# rpi-can-rs485.net
KiCad netlist of a schematic drawn in EAGLE
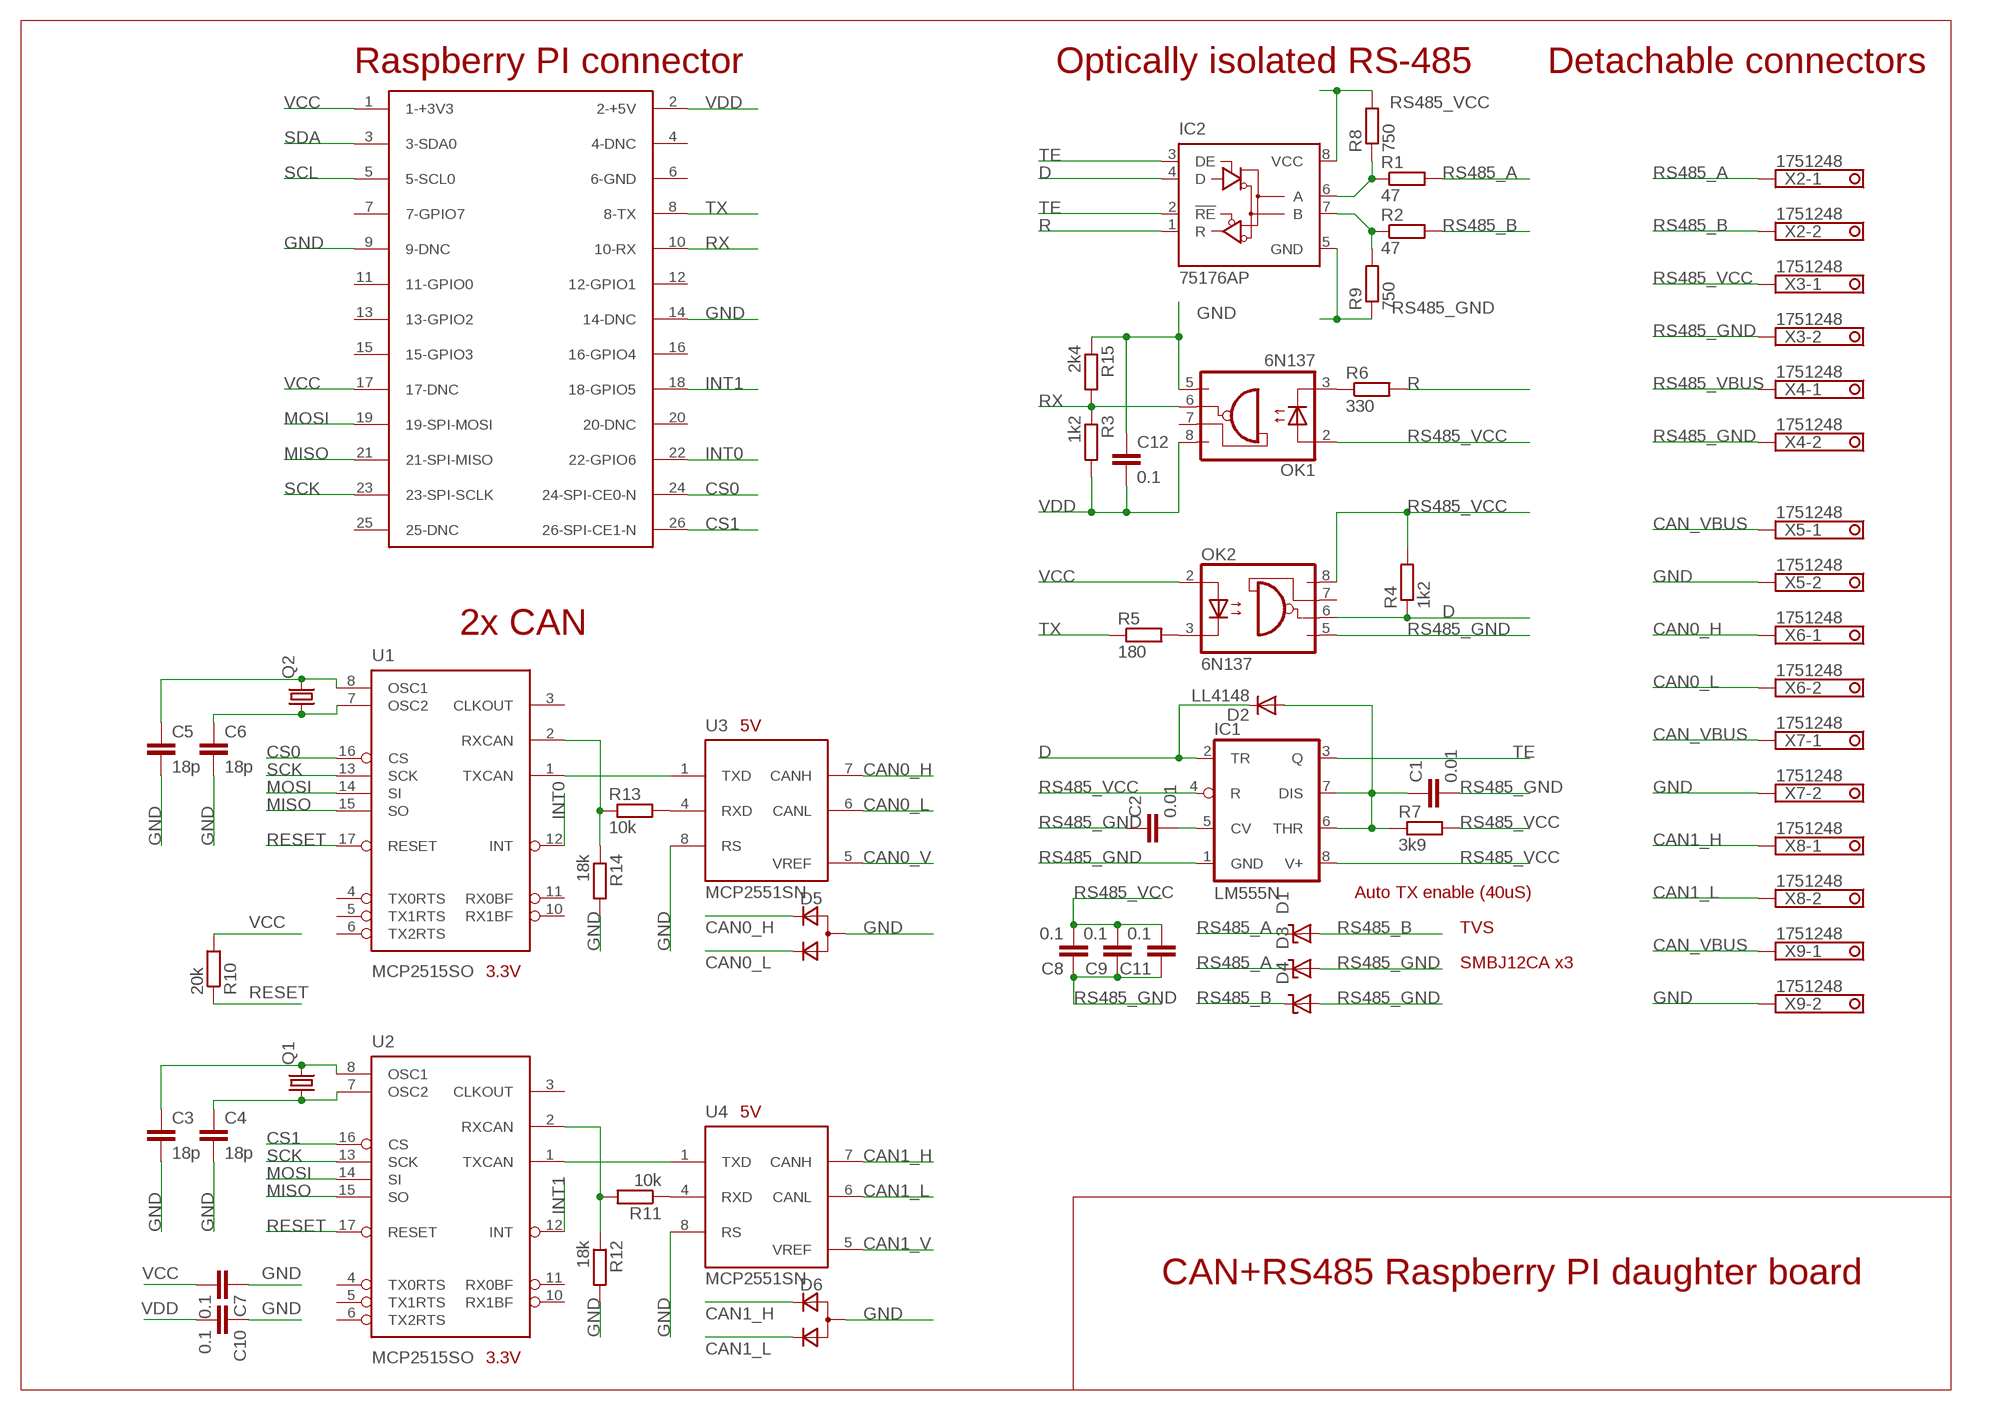
[diagram p0: schematic, sheet 1]

(export (version "E")
  (design (tool "Eeschema 10.0.6"))
  (components
    (comp (ref "C1")
      (value "0.01")
      (footprint "eagle-import:C0805")
      (libsource (lib "eagle-import") (part "C-EUC0805"))
    )
    (comp (ref "C2")
      (value "0.01")
      (footprint "eagle-import:C0805")
      (libsource (lib "eagle-import") (part "C-EUC0805"))
    )
    (comp (ref "C3")
      (value "18p")
      (footprint "eagle-import:C0805")
      (libsource (lib "eagle-import") (part "C-EUC0805"))
    )
    (comp (ref "C4")
      (value "18p")
      (footprint "eagle-import:C0805")
      (libsource (lib "eagle-import") (part "C-EUC0805"))
    )
    (comp (ref "C5")
      (value "18p")
      (footprint "eagle-import:C0805")
      (libsource (lib "eagle-import") (part "C-EUC0805"))
    )
    (comp (ref "C6")
      (value "18p")
      (footprint "eagle-import:C0805")
      (libsource (lib "eagle-import") (part "C-EUC0805"))
    )
    (comp (ref "C7")
      (value "0.1")
      (footprint "eagle-import:C1206")
      (libsource (lib "eagle-import") (part "C-EUC1206"))
    )
    (comp (ref "C8")
      (value "0.1")
      (footprint "eagle-import:C0805")
      (libsource (lib "eagle-import") (part "C-EUC0805"))
    )
    (comp (ref "C9")
      (value "0.1")
      (footprint "eagle-import:C0805")
      (libsource (lib "eagle-import") (part "C-EUC0805"))
    )
    (comp (ref "C10")
      (value "0.1")
      (footprint "eagle-import:C0805")
      (libsource (lib "eagle-import") (part "C-EUC0805"))
    )
    (comp (ref "C11")
      (value "0.1")
      (footprint "eagle-import:C1206")
      (libsource (lib "eagle-import") (part "C-EUC1206"))
    )
    (comp (ref "C12")
      (value "0.1")
      (footprint "eagle-import:C1206")
      (libsource (lib "eagle-import") (part "C-EUC1206"))
    )
    (comp (ref "D1")
      (value "SUPPRESSOR-SMBJ")
      (footprint "eagle-import:SMBJ")
      (libsource (lib "eagle-import") (part "SUPPRESSOR-SMBJ"))
    )
    (comp (ref "D2")
      (value "LL4148")
      (footprint "eagle-import:SOD80C")
      (libsource (lib "eagle-import") (part "DIODE-SOD80C"))
    )
    (comp (ref "D3")
      (value "SUPPRESSOR-SMBJ")
      (footprint "eagle-import:SMBJ")
      (libsource (lib "eagle-import") (part "SUPPRESSOR-SMBJ"))
    )
    (comp (ref "D4")
      (value "SUPPRESSOR-SMBJ")
      (footprint "eagle-import:SMBJ")
      (libsource (lib "eagle-import") (part "SUPPRESSOR-SMBJ"))
    )
    (comp (ref "D5")
      (value "D_2CSOT323")
      (footprint "eagle-import:SOT323")
      (libsource (lib "eagle-import") (part "D_2CSOT323"))
    )
    (comp (ref "D6")
      (value "D_2CSOT323")
      (footprint "eagle-import:SOT323")
      (libsource (lib "eagle-import") (part "D_2CSOT323"))
    )
    (comp (ref "IC1")
      (value "LM555N")
      (footprint "eagle-import:DIL08")
      (libsource (lib "eagle-import") (part "555NLM"))
    )
    (comp (ref "IC2")
      (value "75176AP")
      (footprint "eagle-import:DIL08")
      (libsource (lib "eagle-import") (part "75176AP"))
    )
    (comp (ref "OK1")
      (value "6N137")
      (footprint "eagle-import:DIL08")
      (libsource (lib "eagle-import") (part "6N137"))
    )
    (comp (ref "OK2")
      (value "6N137")
      (footprint "eagle-import:DIL08")
      (libsource (lib "eagle-import") (part "6N137"))
    )
    (comp (ref "Q1")
      (value "CRYSTALHC49S")
      (footprint "eagle-import:HC49_S")
      (libsource (lib "eagle-import") (part "CRYSTALHC49S"))
    )
    (comp (ref "Q2")
      (value "CRYSTALHC49S")
      (footprint "eagle-import:HC49_S")
      (libsource (lib "eagle-import") (part "CRYSTALHC49S"))
    )
    (comp (ref "R1")
      (value "47")
      (footprint "eagle-import:R1206")
      (libsource (lib "eagle-import") (part "R-EU_R1206"))
    )
    (comp (ref "R2")
      (value "47")
      (footprint "eagle-import:R1206")
      (libsource (lib "eagle-import") (part "R-EU_R1206"))
    )
    (comp (ref "R3")
      (value "1k2")
      (footprint "eagle-import:R0805")
      (libsource (lib "eagle-import") (part "R-EU_R0805"))
    )
    (comp (ref "R4")
      (value "1k2")
      (footprint "eagle-import:R0805")
      (libsource (lib "eagle-import") (part "R-EU_R0805"))
    )
    (comp (ref "R5")
      (value "180")
      (footprint "eagle-import:R0805")
      (libsource (lib "eagle-import") (part "R-EU_R0805"))
    )
    (comp (ref "R6")
      (value "330")
      (footprint "eagle-import:R0805")
      (libsource (lib "eagle-import") (part "R-EU_R0805"))
    )
    (comp (ref "R7")
      (value "3k9")
      (footprint "eagle-import:R0805")
      (libsource (lib "eagle-import") (part "R-EU_R0805"))
    )
    (comp (ref "R8")
      (value "750")
      (footprint "eagle-import:R1206")
      (libsource (lib "eagle-import") (part "R-EU_R1206"))
    )
    (comp (ref "R9")
      (value "750")
      (footprint "eagle-import:R1206")
      (libsource (lib "eagle-import") (part "R-EU_R1206"))
    )
    (comp (ref "R10")
      (value "20k")
      (footprint "eagle-import:R0805")
      (libsource (lib "eagle-import") (part "R-EU_R0805"))
    )
    (comp (ref "R11")
      (value "10k")
      (footprint "eagle-import:R0805")
      (libsource (lib "eagle-import") (part "R-EU_R0805"))
    )
    (comp (ref "R12")
      (value "18k")
      (footprint "eagle-import:R0805")
      (libsource (lib "eagle-import") (part "R-EU_R0805"))
    )
    (comp (ref "R13")
      (value "10k")
      (footprint "eagle-import:R0805")
      (libsource (lib "eagle-import") (part "R-EU_R0805"))
    )
    (comp (ref "R14")
      (value "18k")
      (footprint "eagle-import:R0805")
      (libsource (lib "eagle-import") (part "R-EU_R0805"))
    )
    (comp (ref "R15")
      (value "2k4")
      (footprint "eagle-import:R0805")
      (libsource (lib "eagle-import") (part "R-EU_R0805"))
    )
    (comp (ref "U$1")
      (value "RASPBERRY-PI")
      (footprint "eagle-import:RASPBERRY-PI")
      (libsource (lib "eagle-import") (part "RASPBERRY-PI"))
    )
    (comp (ref "U1")
      (value "MCP2515SO")
      (footprint "eagle-import:SO-18W")
      (libsource (lib "eagle-import") (part "MCP2510SO"))
    )
    (comp (ref "U2")
      (value "MCP2515SO")
      (footprint "eagle-import:SO-18W")
      (libsource (lib "eagle-import") (part "MCP2510SO"))
    )
    (comp (ref "U3")
      (value "MCP2551SN")
      (footprint "eagle-import:SO-08")
      (libsource (lib "eagle-import") (part "MCP2551SN"))
    )
    (comp (ref "U4")
      (value "MCP2551SN")
      (footprint "eagle-import:SO-08")
      (libsource (lib "eagle-import") (part "MCP2551SN"))
    )
    (comp (ref "X2")
      (value "1751248")
      (footprint "eagle-import:1751248")
      (libsource (lib "eagle-import") (part "1751248"))
    )
    (comp (ref "X3")
      (value "1751248")
      (footprint "eagle-import:1751248")
      (libsource (lib "eagle-import") (part "1751248"))
    )
    (comp (ref "X4")
      (value "1751248")
      (footprint "eagle-import:1751248")
      (libsource (lib "eagle-import") (part "1751248"))
    )
    (comp (ref "X5")
      (value "1751248")
      (footprint "eagle-import:1751248")
      (libsource (lib "eagle-import") (part "1751248"))
    )
    (comp (ref "X6")
      (value "1751248")
      (footprint "eagle-import:1751248")
      (libsource (lib "eagle-import") (part "1751248"))
    )
    (comp (ref "X7")
      (value "1751248")
      (footprint "eagle-import:1751248")
      (libsource (lib "eagle-import") (part "1751248"))
    )
    (comp (ref "X8")
      (value "1751248")
      (footprint "eagle-import:1751248")
      (libsource (lib "eagle-import") (part "1751248"))
    )
    (comp (ref "X9")
      (value "1751248")
      (footprint "eagle-import:1751248")
      (fields (field (name "OC_FARNELL") "unknown") (field (name "OC_NEWARK") "unknown"))
      (libsource (lib "eagle-import") (part "1751248"))
    )
  )
  (nets
    (net (code "1") (name "/CAN0_H") (class "Default")
      (node (ref "D5") (pin "2") (pinfunction "C1_2") (pintype "passive"))
      (node (ref "U3") (pin "7") (pinfunction "CANH_7") (pintype "bidirectional"))
      (node (ref "X6") (pin "1") (pinfunction "K_1") (pintype "passive"))
    )
    (net (code "2") (name "/CAN0_L") (class "Default")
      (node (ref "D5") (pin "3") (pinfunction "C2_3") (pintype "passive"))
      (node (ref "U3") (pin "6") (pinfunction "CANL_6") (pintype "bidirectional"))
      (node (ref "X6") (pin "2") (pinfunction "K_2") (pintype "passive"))
    )
    (net (code "3") (name "/CAN0_V") (class "Default")
      (node (ref "U3") (pin "5") (pinfunction "VREF_5") (pintype "power_in"))
    )
    (net (code "4") (name "/CAN1_H") (class "Default")
      (node (ref "D6") (pin "2") (pinfunction "C1_2") (pintype "passive"))
      (node (ref "U4") (pin "7") (pinfunction "CANH_7") (pintype "bidirectional"))
      (node (ref "X8") (pin "1") (pinfunction "K_1") (pintype "passive"))
    )
    (net (code "5") (name "/CAN1_L") (class "Default")
      (node (ref "D6") (pin "3") (pinfunction "C2_3") (pintype "passive"))
      (node (ref "U4") (pin "6") (pinfunction "CANL_6") (pintype "bidirectional"))
      (node (ref "X8") (pin "2") (pinfunction "K_2") (pintype "passive"))
    )
    (net (code "6") (name "/CAN1_V") (class "Default")
      (node (ref "U4") (pin "5") (pinfunction "VREF_5") (pintype "power_in"))
    )
    (net (code "7") (name "/CAN_VBUS") (class "Default")
      (node (ref "X5") (pin "1") (pinfunction "K_1") (pintype "passive"))
      (node (ref "X7") (pin "1") (pinfunction "K_1") (pintype "passive"))
      (node (ref "X9") (pin "1") (pinfunction "K_1") (pintype "passive"))
    )
    (net (code "8") (name "/CS0") (class "Default")
      (node (ref "U$1") (pin "24") (pinfunction "24-SPI-CE0-N_24") (pintype "bidirectional"))
      (node (ref "U1") (pin "16") (pinfunction "CS_16") (pintype "input"))
    )
    (net (code "9") (name "/CS1") (class "Default")
      (node (ref "U$1") (pin "26") (pinfunction "26-SPI-CE1-N_26") (pintype "bidirectional"))
      (node (ref "U2") (pin "16") (pinfunction "CS_16") (pintype "input"))
    )
    (net (code "10") (name "/D") (class "Default")
      (node (ref "D2") (pin "C") (pinfunction "C_C") (pintype "passive"))
      (node (ref "IC1") (pin "2") (pinfunction "TR_2") (pintype "input"))
      (node (ref "IC2") (pin "4") (pinfunction "D_4") (pintype "input"))
      (node (ref "OK2") (pin "6") (pinfunction "VO_6") (pintype "passive"))
      (node (ref "R4") (pin "1") (pinfunction "1_1") (pintype "passive"))
    )
    (net (code "11") (name "/GND") (class "Default")
      (node (ref "C10") (pin "1") (pinfunction "1_1") (pintype "passive"))
      (node (ref "C12") (pin "1") (pinfunction "1_1") (pintype "passive"))
      (node (ref "C3") (pin "2") (pinfunction "2_2") (pintype "passive"))
      (node (ref "C4") (pin "2") (pinfunction "2_2") (pintype "passive"))
      (node (ref "C5") (pin "2") (pinfunction "2_2") (pintype "passive"))
      (node (ref "C6") (pin "2") (pinfunction "2_2") (pintype "passive"))
      (node (ref "C7") (pin "1") (pinfunction "1_1") (pintype "passive"))
      (node (ref "D5") (pin "1") (pinfunction "A_1") (pintype "passive"))
      (node (ref "D6") (pin "1") (pinfunction "A_1") (pintype "passive"))
      (node (ref "OK1") (pin "5") (pinfunction "GND_5") (pintype "passive"))
      (node (ref "R12") (pin "2") (pinfunction "2_2") (pintype "passive"))
      (node (ref "R14") (pin "2") (pinfunction "2_2") (pintype "passive"))
      (node (ref "R15") (pin "1") (pinfunction "1_1") (pintype "passive"))
      (node (ref "U$1") (pin "14") (pinfunction "14-DNC_14") (pintype "bidirectional"))
      (node (ref "U$1") (pin "9") (pinfunction "9-DNC_9") (pintype "bidirectional"))
      (node (ref "U3") (pin "8") (pinfunction "RS_8") (pintype "input"))
      (node (ref "U4") (pin "8") (pinfunction "RS_8") (pintype "input"))
      (node (ref "X5") (pin "2") (pinfunction "K_2") (pintype "passive"))
      (node (ref "X7") (pin "2") (pinfunction "K_2") (pintype "passive"))
      (node (ref "X9") (pin "2") (pinfunction "K_2") (pintype "passive"))
    )
    (net (code "12") (name "/INT0") (class "Default")
      (node (ref "U$1") (pin "22") (pinfunction "22-GPIO6_22") (pintype "bidirectional"))
      (node (ref "U1") (pin "12") (pinfunction "INT_12") (pintype "output"))
    )
    (net (code "13") (name "/INT1") (class "Default")
      (node (ref "U$1") (pin "18") (pinfunction "18-GPIO5_18") (pintype "bidirectional"))
      (node (ref "U2") (pin "12") (pinfunction "INT_12") (pintype "output"))
    )
    (net (code "14") (name "/MISO") (class "Default")
      (node (ref "U$1") (pin "21") (pinfunction "21-SPI-MISO_21") (pintype "bidirectional"))
      (node (ref "U1") (pin "15") (pinfunction "SO_15") (pintype "output"))
      (node (ref "U2") (pin "15") (pinfunction "SO_15") (pintype "output"))
    )
    (net (code "15") (name "/MOSI") (class "Default")
      (node (ref "U$1") (pin "19") (pinfunction "19-SPI-MOSI_19") (pintype "bidirectional"))
      (node (ref "U1") (pin "14") (pinfunction "SI_14") (pintype "input"))
      (node (ref "U2") (pin "14") (pinfunction "SI_14") (pintype "input"))
    )
    (net (code "16") (name "/R") (class "Default")
      (node (ref "IC2") (pin "1") (pinfunction "R_1") (pintype "input"))
      (node (ref "R6") (pin "2") (pinfunction "2_2") (pintype "passive"))
    )
    (net (code "17") (name "/RESET") (class "Default")
      (node (ref "R10") (pin "1") (pinfunction "1_1") (pintype "passive"))
      (node (ref "U1") (pin "17") (pinfunction "RESET_17") (pintype "input"))
      (node (ref "U2") (pin "17") (pinfunction "RESET_17") (pintype "input"))
    )
    (net (code "18") (name "/RS485_A") (class "Default")
      (node (ref "D1") (pin "C") (pinfunction "C_C") (pintype "passive"))
      (node (ref "D3") (pin "C") (pinfunction "C_C") (pintype "passive"))
      (node (ref "R1") (pin "2") (pinfunction "2_2") (pintype "passive"))
      (node (ref "X2") (pin "1") (pinfunction "K_1") (pintype "passive"))
    )
    (net (code "19") (name "/RS485_B") (class "Default")
      (node (ref "D1") (pin "A") (pinfunction "A_A") (pintype "passive"))
      (node (ref "D4") (pin "C") (pinfunction "C_C") (pintype "passive"))
      (node (ref "R2") (pin "2") (pinfunction "2_2") (pintype "passive"))
      (node (ref "X2") (pin "2") (pinfunction "K_2") (pintype "passive"))
    )
    (net (code "20") (name "/RS485_GND") (class "Default")
      (node (ref "C1") (pin "2") (pinfunction "2_2") (pintype "passive"))
      (node (ref "C11") (pin "1") (pinfunction "1_1") (pintype "passive"))
      (node (ref "C2") (pin "1") (pinfunction "1_1") (pintype "passive"))
      (node (ref "C8") (pin "1") (pinfunction "1_1") (pintype "passive"))
      (node (ref "C9") (pin "1") (pinfunction "1_1") (pintype "passive"))
      (node (ref "D3") (pin "A") (pinfunction "A_A") (pintype "passive"))
      (node (ref "D4") (pin "A") (pinfunction "A_A") (pintype "passive"))
      (node (ref "IC1") (pin "1") (pinfunction "GND_1") (pintype "power_in"))
      (node (ref "IC2") (pin "5") (pinfunction "GND_5") (pintype "power_in"))
      (node (ref "OK2") (pin "5") (pinfunction "GND_5") (pintype "passive"))
      (node (ref "R9") (pin "1") (pinfunction "1_1") (pintype "passive"))
      (node (ref "X3") (pin "2") (pinfunction "K_2") (pintype "passive"))
      (node (ref "X4") (pin "2") (pinfunction "K_2") (pintype "passive"))
    )
    (net (code "21") (name "/RS485_VBUS") (class "Default")
      (node (ref "X4") (pin "1") (pinfunction "K_1") (pintype "passive"))
    )
    (net (code "22") (name "/RS485_VCC") (class "Default")
      (node (ref "C11") (pin "2") (pinfunction "2_2") (pintype "passive"))
      (node (ref "C8") (pin "2") (pinfunction "2_2") (pintype "passive"))
      (node (ref "C9") (pin "2") (pinfunction "2_2") (pintype "passive"))
      (node (ref "IC1") (pin "4") (pinfunction "R_4") (pintype "input"))
      (node (ref "IC1") (pin "8") (pinfunction "V+_8") (pintype "power_in"))
      (node (ref "IC2") (pin "8") (pinfunction "VCC_8") (pintype "power_in"))
      (node (ref "OK1") (pin "2") (pinfunction "A_2") (pintype "passive"))
      (node (ref "OK2") (pin "8") (pinfunction "VCC_8") (pintype "passive"))
      (node (ref "R4") (pin "2") (pinfunction "2_2") (pintype "passive"))
      (node (ref "R7") (pin "2") (pinfunction "2_2") (pintype "passive"))
      (node (ref "R8") (pin "2") (pinfunction "2_2") (pintype "passive"))
      (node (ref "X3") (pin "1") (pinfunction "K_1") (pintype "passive"))
    )
    (net (code "23") (name "/RX") (class "Default")
      (node (ref "OK1") (pin "6") (pinfunction "VO_6") (pintype "passive"))
      (node (ref "R15") (pin "2") (pinfunction "2_2") (pintype "passive"))
      (node (ref "R3") (pin "1") (pinfunction "1_1") (pintype "passive"))
      (node (ref "U$1") (pin "10") (pinfunction "10-RX_10") (pintype "bidirectional"))
    )
    (net (code "24") (name "/SCK") (class "Default")
      (node (ref "U$1") (pin "23") (pinfunction "23-SPI-SCLK_23") (pintype "bidirectional"))
      (node (ref "U1") (pin "13") (pinfunction "SCK_13") (pintype "input"))
      (node (ref "U2") (pin "13") (pinfunction "SCK_13") (pintype "input"))
    )
    (net (code "25") (name "/SCL") (class "Default")
      (node (ref "U$1") (pin "5") (pinfunction "5-SCL0_5") (pintype "bidirectional"))
    )
    (net (code "26") (name "/SDA") (class "Default")
      (node (ref "U$1") (pin "3") (pinfunction "3-SDA0_3") (pintype "bidirectional"))
    )
    (net (code "27") (name "/TE") (class "Default")
      (node (ref "IC1") (pin "3") (pinfunction "Q_3") (pintype "output"))
      (node (ref "IC2") (pin "2") (pinfunction "~{RE}_2") (pintype "input"))
      (node (ref "IC2") (pin "3") (pinfunction "DE_3") (pintype "input"))
    )
    (net (code "28") (name "/TX") (class "Default")
      (node (ref "R5") (pin "1") (pinfunction "1_1") (pintype "passive"))
      (node (ref "U$1") (pin "8") (pinfunction "8-TX_8") (pintype "bidirectional"))
    )
    (net (code "29") (name "/VCC") (class "Default")
      (node (ref "C7") (pin "2") (pinfunction "2_2") (pintype "passive"))
      (node (ref "OK2") (pin "2") (pinfunction "A_2") (pintype "passive"))
      (node (ref "R10") (pin "2") (pinfunction "2_2") (pintype "passive"))
      (node (ref "U$1") (pin "1") (pinfunction "1-+3V3_1") (pintype "bidirectional"))
      (node (ref "U$1") (pin "17") (pinfunction "17-DNC_17") (pintype "bidirectional"))
    )
    (net (code "30") (name "/VDD") (class "Default")
      (node (ref "C10") (pin "2") (pinfunction "2_2") (pintype "passive"))
      (node (ref "C12") (pin "2") (pinfunction "2_2") (pintype "passive"))
      (node (ref "OK1") (pin "8") (pinfunction "VCC_8") (pintype "passive"))
      (node (ref "R3") (pin "2") (pinfunction "2_2") (pintype "passive"))
      (node (ref "U$1") (pin "2") (pinfunction "2-+5V_2") (pintype "bidirectional"))
    )
    (net (code "31") (name "Net-(IC1-CV)") (class "Default")
      (node (ref "C2") (pin "2") (pinfunction "2_2") (pintype "passive"))
      (node (ref "IC1") (pin "5") (pinfunction "CV_5") (pintype "input"))
    )
    (net (code "32") (name "Net-(IC1-DIS)") (class "Default")
      (node (ref "C1") (pin "1") (pinfunction "1_1") (pintype "passive"))
      (node (ref "D2") (pin "A") (pinfunction "A_A") (pintype "passive"))
      (node (ref "IC1") (pin "6") (pinfunction "THR_6") (pintype "input"))
      (node (ref "IC1") (pin "7") (pinfunction "DIS_7") (pintype "input"))
      (node (ref "R7") (pin "1") (pinfunction "1_1") (pintype "passive"))
    )
    (net (code "33") (name "Net-(IC2-A)") (class "Default")
      (node (ref "IC2") (pin "6") (pinfunction "A_6") (pintype "output"))
      (node (ref "R1") (pin "1") (pinfunction "1_1") (pintype "passive"))
      (node (ref "R8") (pin "1") (pinfunction "1_1") (pintype "passive"))
    )
    (net (code "34") (name "Net-(IC2-B)") (class "Default")
      (node (ref "IC2") (pin "7") (pinfunction "B_7") (pintype "output"))
      (node (ref "R2") (pin "1") (pinfunction "1_1") (pintype "passive"))
      (node (ref "R9") (pin "2") (pinfunction "2_2") (pintype "passive"))
    )
    (net (code "35") (name "Net-(OK1-C)") (class "Default")
      (node (ref "OK1") (pin "3") (pinfunction "C_3") (pintype "passive"))
      (node (ref "R6") (pin "1") (pinfunction "1_1") (pintype "passive"))
    )
    (net (code "36") (name "Net-(OK2-C)") (class "Default")
      (node (ref "OK2") (pin "3") (pinfunction "C_3") (pintype "passive"))
      (node (ref "R5") (pin "2") (pinfunction "2_2") (pintype "passive"))
    )
    (net (code "37") (name "Net-(U1A-OSC1)") (class "Default")
      (node (ref "C5") (pin "1") (pinfunction "1_1") (pintype "passive"))
      (node (ref "Q2") (pin "2") (pinfunction "2_2") (pintype "passive"))
      (node (ref "U1") (pin "8") (pinfunction "OSC1_8") (pintype "input"))
    )
    (net (code "38") (name "Net-(U1A-OSC2)") (class "Default")
      (node (ref "C6") (pin "1") (pinfunction "1_1") (pintype "passive"))
      (node (ref "Q2") (pin "1") (pinfunction "1_1") (pintype "passive"))
      (node (ref "U1") (pin "7") (pinfunction "OSC2_7") (pintype "output"))
    )
    (net (code "39") (name "Net-(U1A-RXCAN)") (class "Default")
      (node (ref "R13") (pin "1") (pinfunction "1_1") (pintype "passive"))
      (node (ref "R14") (pin "1") (pinfunction "1_1") (pintype "passive"))
      (node (ref "U1") (pin "2") (pinfunction "RXCAN_2") (pintype "input"))
    )
    (net (code "40") (name "Net-(U1A-TXCAN)") (class "Default")
      (node (ref "U1") (pin "1") (pinfunction "TXCAN_1") (pintype "output"))
      (node (ref "U3") (pin "1") (pinfunction "TXD_1") (pintype "input"))
    )
    (net (code "41") (name "Net-(U2A-OSC1)") (class "Default")
      (node (ref "C3") (pin "1") (pinfunction "1_1") (pintype "passive"))
      (node (ref "Q1") (pin "2") (pinfunction "2_2") (pintype "passive"))
      (node (ref "U2") (pin "8") (pinfunction "OSC1_8") (pintype "input"))
    )
    (net (code "42") (name "Net-(U2A-OSC2)") (class "Default")
      (node (ref "C4") (pin "1") (pinfunction "1_1") (pintype "passive"))
      (node (ref "Q1") (pin "1") (pinfunction "1_1") (pintype "passive"))
      (node (ref "U2") (pin "7") (pinfunction "OSC2_7") (pintype "output"))
    )
    (net (code "43") (name "Net-(U2A-RXCAN)") (class "Default")
      (node (ref "R11") (pin "2") (pinfunction "2_2") (pintype "passive"))
      (node (ref "R12") (pin "1") (pinfunction "1_1") (pintype "passive"))
      (node (ref "U2") (pin "2") (pinfunction "RXCAN_2") (pintype "input"))
    )
    (net (code "44") (name "Net-(U2A-TXCAN)") (class "Default")
      (node (ref "U2") (pin "1") (pinfunction "TXCAN_1") (pintype "output"))
      (node (ref "U4") (pin "1") (pinfunction "TXD_1") (pintype "input"))
    )
    (net (code "45") (name "Net-(U3A-RXD)") (class "Default")
      (node (ref "R13") (pin "2") (pinfunction "2_2") (pintype "passive"))
      (node (ref "U3") (pin "4") (pinfunction "RXD_4") (pintype "output"))
    )
    (net (code "46") (name "Net-(U4A-RXD)") (class "Default")
      (node (ref "R11") (pin "1") (pinfunction "1_1") (pintype "passive"))
      (node (ref "U4") (pin "4") (pinfunction "RXD_4") (pintype "output"))
    )
    (net (code "47") (name "unconnected-(OK1-VE-Pad7)") (class "Default")
      (node (ref "OK1") (pin "7") (pinfunction "VE_7") (pintype "passive"))
    )
    (net (code "48") (name "unconnected-(OK2-VE-Pad7)") (class "Default")
      (node (ref "OK2") (pin "7") (pinfunction "VE_7") (pintype "passive"))
    )
    (net (code "49") (name "unconnected-(U$1-4-DNC-Pad4)") (class "Default")
      (node (ref "U$1") (pin "4") (pinfunction "4-DNC_4") (pintype "bidirectional"))
    )
    (net (code "50") (name "unconnected-(U$1-6-GND-Pad6)") (class "Default")
      (node (ref "U$1") (pin "6") (pinfunction "6-GND_6") (pintype "bidirectional"))
    )
    (net (code "51") (name "unconnected-(U$1-7-GPIO7-Pad7)") (class "Default")
      (node (ref "U$1") (pin "7") (pinfunction "7-GPIO7_7") (pintype "bidirectional"))
    )
    (net (code "52") (name "unconnected-(U$1-11-GPIO0-Pad11)") (class "Default")
      (node (ref "U$1") (pin "11") (pinfunction "11-GPIO0_11") (pintype "bidirectional"))
    )
    (net (code "53") (name "unconnected-(U$1-12-GPIO1-Pad12)") (class "Default")
      (node (ref "U$1") (pin "12") (pinfunction "12-GPIO1_12") (pintype "bidirectional"))
    )
    (net (code "54") (name "unconnected-(U$1-13-GPIO2-Pad13)") (class "Default")
      (node (ref "U$1") (pin "13") (pinfunction "13-GPIO2_13") (pintype "bidirectional"))
    )
    (net (code "55") (name "unconnected-(U$1-15-GPIO3-Pad15)") (class "Default")
      (node (ref "U$1") (pin "15") (pinfunction "15-GPIO3_15") (pintype "bidirectional"))
    )
    (net (code "56") (name "unconnected-(U$1-16-GPIO4-Pad16)") (class "Default")
      (node (ref "U$1") (pin "16") (pinfunction "16-GPIO4_16") (pintype "bidirectional"))
    )
    (net (code "57") (name "unconnected-(U$1-20-DNC-Pad20)") (class "Default")
      (node (ref "U$1") (pin "20") (pinfunction "20-DNC_20") (pintype "bidirectional"))
    )
    (net (code "58") (name "unconnected-(U$1-25-DNC-Pad25)") (class "Default")
      (node (ref "U$1") (pin "25") (pinfunction "25-DNC_25") (pintype "bidirectional"))
    )
    (net (code "59") (name "unconnected-(U1A-CLKOUT-Pad3)") (class "Default")
      (node (ref "U1") (pin "3") (pinfunction "CLKOUT_3") (pintype "output"))
    )
    (net (code "60") (name "unconnected-(U1A-RX0BF-Pad11)") (class "Default")
      (node (ref "U1") (pin "11") (pinfunction "RX0BF_11") (pintype "output"))
    )
    (net (code "61") (name "unconnected-(U1A-RX1BF-Pad10)") (class "Default")
      (node (ref "U1") (pin "10") (pinfunction "RX1BF_10") (pintype "output"))
    )
    (net (code "62") (name "unconnected-(U1A-TX0RTS-Pad4)") (class "Default")
      (node (ref "U1") (pin "4") (pinfunction "TX0RTS_4") (pintype "input"))
    )
    (net (code "63") (name "unconnected-(U1A-TX1RTS-Pad5)") (class "Default")
      (node (ref "U1") (pin "5") (pinfunction "TX1RTS_5") (pintype "input"))
    )
    (net (code "64") (name "unconnected-(U1A-TX2RTS-Pad6)") (class "Default")
      (node (ref "U1") (pin "6") (pinfunction "TX2RTS_6") (pintype "input"))
    )
    (net (code "65") (name "unconnected-(U2A-CLKOUT-Pad3)") (class "Default")
      (node (ref "U2") (pin "3") (pinfunction "CLKOUT_3") (pintype "output"))
    )
    (net (code "66") (name "unconnected-(U2A-RX0BF-Pad11)") (class "Default")
      (node (ref "U2") (pin "11") (pinfunction "RX0BF_11") (pintype "output"))
    )
    (net (code "67") (name "unconnected-(U2A-RX1BF-Pad10)") (class "Default")
      (node (ref "U2") (pin "10") (pinfunction "RX1BF_10") (pintype "output"))
    )
    (net (code "68") (name "unconnected-(U2A-TX0RTS-Pad4)") (class "Default")
      (node (ref "U2") (pin "4") (pinfunction "TX0RTS_4") (pintype "input"))
    )
    (net (code "69") (name "unconnected-(U2A-TX1RTS-Pad5)") (class "Default")
      (node (ref "U2") (pin "5") (pinfunction "TX1RTS_5") (pintype "input"))
    )
    (net (code "70") (name "unconnected-(U2A-TX2RTS-Pad6)") (class "Default")
      (node (ref "U2") (pin "6") (pinfunction "TX2RTS_6") (pintype "input"))
    )
  )
)
